# ff.net
KiCad netlist of a schematic drawn in Altium Designer
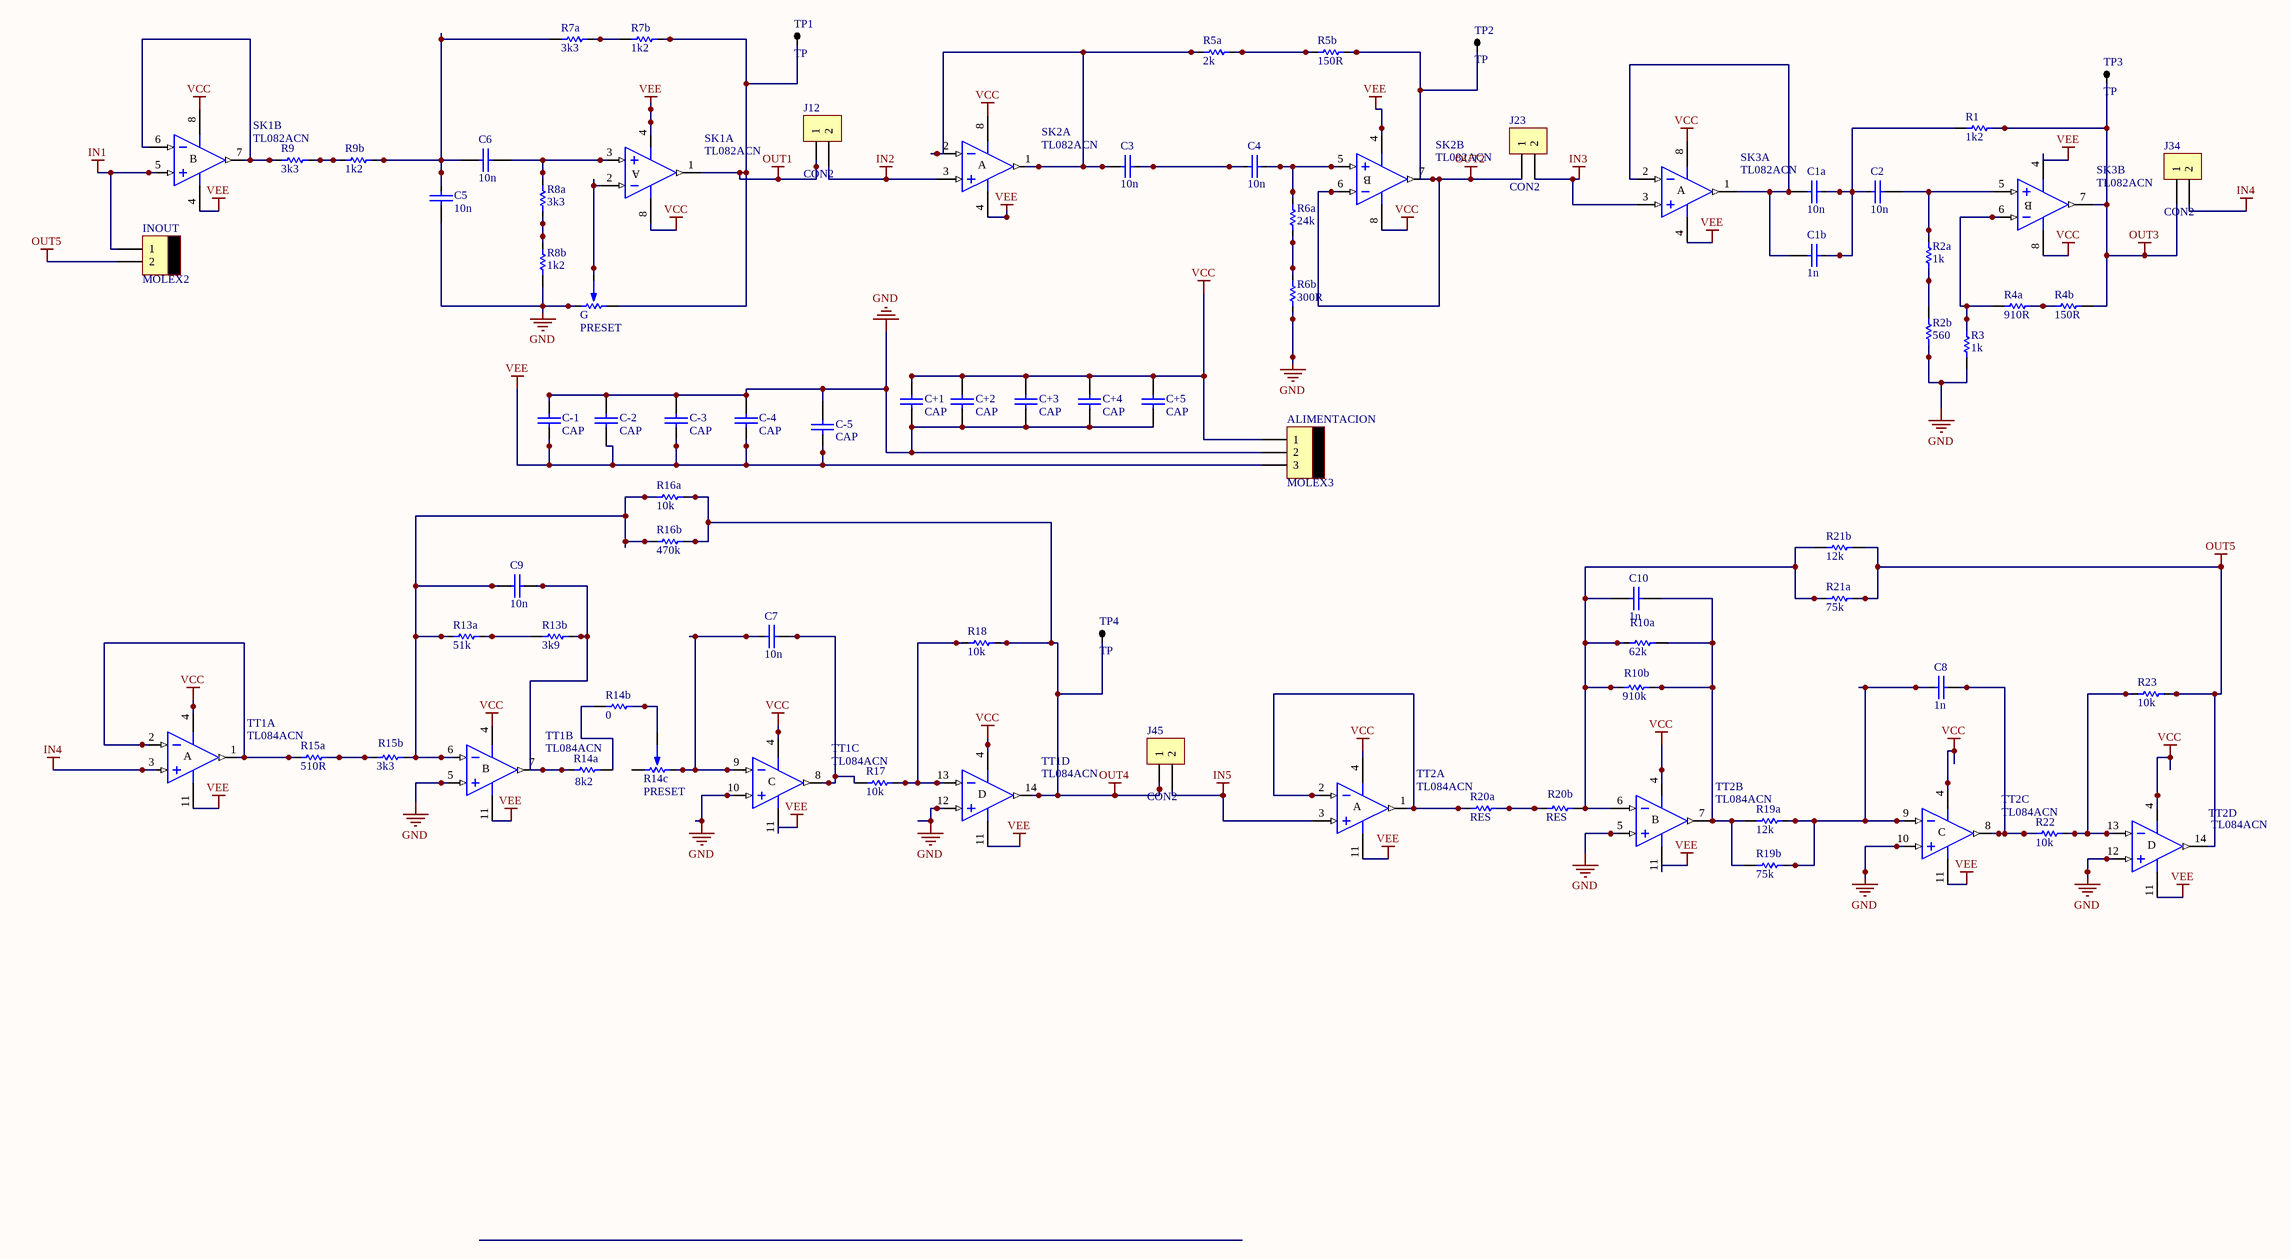
[diagram p0: ff.SchDoc]

(export (version "E")
  (design (tool "Eeschema 10.0.6"))
  (components
    (comp (ref "ALIMENTACION")
      (value "MOLEX3")
      (footprint "MOLEX3")
      (libsource (lib "LIBEBAL") (part "MOLEX3"))
    )
    (comp (ref "C+1") (value "CAP") (footprint "CAP200") (libsource (lib "LIBEBAL") (part "CAP")))
    (comp (ref "C+2") (value "CAP") (footprint "CAP200") (libsource (lib "LIBEBAL") (part "CAP")))
    (comp (ref "C+3") (value "CAP") (footprint "CAP200") (libsource (lib "LIBEBAL") (part "CAP")))
    (comp (ref "C+4") (value "CAP") (footprint "CAP200") (libsource (lib "LIBEBAL") (part "CAP")))
    (comp (ref "C+5") (value "CAP") (footprint "CAP200") (libsource (lib "LIBEBAL") (part "CAP")))
    (comp (ref "C-1") (value "CAP") (footprint "CAP200") (libsource (lib "LIBEBAL") (part "CAP")))
    (comp (ref "C-2") (value "CAP") (footprint "CAP200") (libsource (lib "LIBEBAL") (part "CAP")))
    (comp (ref "C-3") (value "CAP") (footprint "CAP200") (libsource (lib "LIBEBAL") (part "CAP")))
    (comp (ref "C-4") (value "CAP") (footprint "CAP200") (libsource (lib "LIBEBAL") (part "CAP")))
    (comp (ref "C-5") (value "CAP") (footprint "CAP200") (libsource (lib "LIBEBAL") (part "CAP")))
    (comp (ref "C1a") (value "10n") (footprint "CAP200") (libsource (lib "LIBEBAL") (part "CAP")))
    (comp (ref "C1b") (value "1n") (footprint "CAP200") (libsource (lib "LIBEBAL") (part "CAP")))
    (comp (ref "C2") (value "10n") (footprint "CAP200") (libsource (lib "LIBEBAL") (part "CAP")))
    (comp (ref "C3") (value "10n") (footprint "CAP200") (libsource (lib "LIBEBAL") (part "CAP")))
    (comp (ref "C4") (value "10n") (footprint "CAP200") (libsource (lib "LIBEBAL") (part "CAP")))
    (comp (ref "C5") (value "10n") (footprint "CAP200") (libsource (lib "LIBEBAL") (part "CAP")))
    (comp (ref "C6") (value "10n") (footprint "CAP200") (libsource (lib "LIBEBAL") (part "CAP")))
    (comp (ref "C7") (value "10n") (footprint "CAP200") (libsource (lib "LIBEBAL") (part "CAP")))
    (comp (ref "C8") (value "1n") (footprint "CAP200") (libsource (lib "LIBEBAL") (part "CAP")))
    (comp (ref "C9") (value "10n") (footprint "CAP200") (libsource (lib "LIBEBAL") (part "CAP")))
    (comp (ref "C10") (value "1n") (footprint "CAP200") (libsource (lib "LIBEBAL") (part "CAP")))
    (comp (ref "G") (value "PRESET") (footprint "PRESET V") (libsource (lib "LIBEBAL") (part "PRESET")))
    (comp (ref "INOUT") (value "MOLEX2") (footprint "MOLEX2") (libsource (lib "LIBEBAL") (part "MOLEX2")))
    (comp (ref "J12") (value "CON2") (footprint "SIP2") (libsource (lib "LIBEBAL") (part "CON2")))
    (comp (ref "J23") (value "CON2") (footprint "SIP2") (libsource (lib "LIBEBAL") (part "CON2")))
    (comp (ref "J34") (value "CON2") (footprint "SIP2") (libsource (lib "LIBEBAL") (part "CON2")))
    (comp (ref "J45") (value "CON2") (footprint "SIP2") (libsource (lib "LIBEBAL") (part "CON2")))
    (comp (ref "R1") (value "1k2") (footprint "0805") (libsource (lib "LIBEBAL") (part "RES")))
    (comp (ref "R2a") (value "1k") (footprint "0805") (libsource (lib "LIBEBAL") (part "RES")))
    (comp (ref "R2b") (value "560") (footprint "0805") (libsource (lib "LIBEBAL") (part "RES")))
    (comp (ref "R3") (value "1k") (footprint "0805") (libsource (lib "LIBEBAL") (part "RES")))
    (comp (ref "R4a") (value "910R") (footprint "0805") (libsource (lib "LIBEBAL") (part "RES")))
    (comp (ref "R4b") (value "150R") (footprint "0805") (libsource (lib "LIBEBAL") (part "RES")))
    (comp (ref "R5a") (value "2k") (footprint "0805") (libsource (lib "LIBEBAL") (part "RES")))
    (comp (ref "R5b") (value "150R") (footprint "0805") (libsource (lib "LIBEBAL") (part "RES")))
    (comp (ref "R6a") (value "24k") (footprint "0805") (libsource (lib "LIBEBAL") (part "RES")))
    (comp (ref "R6b") (value "300R") (footprint "0805") (libsource (lib "LIBEBAL") (part "RES")))
    (comp (ref "R7a") (value "3k3") (footprint "0805") (libsource (lib "LIBEBAL") (part "RES")))
    (comp (ref "R7b") (value "1k2") (footprint "0805") (libsource (lib "LIBEBAL") (part "RES")))
    (comp (ref "R8a") (value "3k3") (footprint "0805") (libsource (lib "LIBEBAL") (part "RES")))
    (comp (ref "R8b") (value "1k2") (footprint "0805") (libsource (lib "LIBEBAL") (part "RES")))
    (comp (ref "R9") (value "3k3") (footprint "0805") (libsource (lib "LIBEBAL") (part "RES")))
    (comp (ref "R9b") (value "1k2") (footprint "0805") (libsource (lib "LIBEBAL") (part "RES")))
    (comp (ref "R10a") (value "62k") (footprint "0805") (libsource (lib "LIBEBAL") (part "RES")))
    (comp (ref "R10b") (value "910k") (footprint "0805") (libsource (lib "LIBEBAL") (part "RES")))
    (comp (ref "R13a") (value "51k") (footprint "0805") (libsource (lib "LIBEBAL") (part "RES")))
    (comp (ref "R13b") (value "3k9") (footprint "0805") (libsource (lib "LIBEBAL") (part "RES")))
    (comp (ref "R14a") (value "8k2") (footprint "0805") (libsource (lib "LIBEBAL") (part "RES")))
    (comp (ref "R14b") (value "0") (footprint "0805") (libsource (lib "LIBEBAL") (part "RES")))
    (comp (ref "R14c") (value "PRESET") (footprint "PRESET V") (libsource (lib "LIBEBAL") (part "PRESET")))
    (comp (ref "R15a") (value "510R") (footprint "0805") (libsource (lib "LIBEBAL") (part "RES")))
    (comp (ref "R15b") (value "3k3") (footprint "0805") (libsource (lib "LIBEBAL") (part "RES")))
    (comp (ref "R16a") (value "10k") (footprint "0805") (libsource (lib "LIBEBAL") (part "RES")))
    (comp (ref "R16b") (value "470k") (footprint "0805") (libsource (lib "LIBEBAL") (part "RES")))
    (comp (ref "R17") (value "10k") (footprint "0805") (libsource (lib "LIBEBAL") (part "RES")))
    (comp (ref "R18") (value "10k") (footprint "0805") (libsource (lib "LIBEBAL") (part "RES")))
    (comp (ref "R19a") (value "12k") (footprint "0805") (libsource (lib "LIBEBAL") (part "RES")))
    (comp (ref "R19b") (value "75k") (footprint "0805") (libsource (lib "LIBEBAL") (part "RES")))
    (comp (ref "R20a") (value "RES") (footprint "0805") (libsource (lib "LIBEBAL") (part "RES")))
    (comp (ref "R20b") (value "RES") (footprint "0805") (libsource (lib "LIBEBAL") (part "RES")))
    (comp (ref "R21a") (value "75k") (footprint "0805") (libsource (lib "LIBEBAL") (part "RES")))
    (comp (ref "R21b") (value "12k") (footprint "0805") (libsource (lib "LIBEBAL") (part "RES")))
    (comp (ref "R22") (value "10k") (footprint "0805") (libsource (lib "LIBEBAL") (part "RES")))
    (comp (ref "R23") (value "10k") (footprint "0805") (libsource (lib "LIBEBAL") (part "RES")))
    (comp (ref "SK1")
      (value "TL082ACN")
      (footprint "DIP8")
      (description "General-Purpose J-FET Dual Operational Amplifier")
      (fields (field (name "PUBLISHER") "Altium Limited"))
      (libsource (lib "ST Operational Amplifier") (part "TL082ACN"))
    )
    (comp (ref "SK2")
      (value "TL082ACN")
      (footprint "DIP8")
      (description "General-Purpose J-FET Dual Operational Amplifier")
      (fields (field (name "PUBLISHER") "Altium Limited"))
      (libsource (lib "ST Operational Amplifier") (part "TL082ACN"))
    )
    (comp (ref "SK3")
      (value "TL082ACN")
      (footprint "DIP8")
      (description "General-Purpose J-FET Dual Operational Amplifier")
      (fields (field (name "PUBLISHER") "Altium Limited"))
      (libsource (lib "ST Operational Amplifier") (part "TL082ACN"))
    )
    (comp (ref "TP1") (value "TP") (footprint "TPTH") (libsource (lib "LIBEBAL") (part "TP")))
    (comp (ref "TP2") (value "TP") (footprint "TPTH") (libsource (lib "LIBEBAL") (part "TP")))
    (comp (ref "TP3") (value "TP") (footprint "TPTH") (libsource (lib "LIBEBAL") (part "TP")))
    (comp (ref "TP4") (value "TP") (footprint "TPTH") (libsource (lib "LIBEBAL") (part "TP")))
    (comp (ref "TT1")
      (value "TL084ACN")
      (footprint "DIP14")
      (description "General-Purpose J-FET Quad Operational Amplifier")
      (fields (field (name "PUBLISHER") "Altium Limited"))
      (libsource (lib "ST Operational Amplifier") (part "TL084ACN"))
    )
    (comp (ref "TT2")
      (value "TL084ACN")
      (footprint "DIP14")
      (description "General-Purpose J-FET Quad Operational Amplifier")
      (fields (field (name "PUBLISHER") "Altium Limited"))
      (libsource (lib "ST Operational Amplifier") (part "TL084ACN"))
    )
  )
  (nets
    (net (code "1") (name "GND") (class "Default")
      (node (ref "ALIMENTACION") (pin "2") (pinfunction "2_2") (pintype "passive"))
      (node (ref "C+1") (pin "2") (pinfunction "2_2") (pintype "passive"))
      (node (ref "C+2") (pin "2") (pinfunction "2_2") (pintype "passive"))
      (node (ref "C+3") (pin "2") (pinfunction "2_2") (pintype "passive"))
      (node (ref "C+4") (pin "2") (pinfunction "2_2") (pintype "passive"))
      (node (ref "C+5") (pin "2") (pinfunction "2_2") (pintype "passive"))
      (node (ref "C-1") (pin "1") (pinfunction "1_1") (pintype "passive"))
      (node (ref "C-2") (pin "1") (pinfunction "1_1") (pintype "passive"))
      (node (ref "C-3") (pin "1") (pinfunction "1_1") (pintype "passive"))
      (node (ref "C-4") (pin "1") (pinfunction "1_1") (pintype "passive"))
      (node (ref "C-5") (pin "1") (pinfunction "1_1") (pintype "passive"))
      (node (ref "C5") (pin "1") (pinfunction "1_1") (pintype "passive"))
      (node (ref "G") (pin "1") (pinfunction "1_1") (pintype "passive"))
      (node (ref "R2b") (pin "1") (pinfunction "1_1") (pintype "passive"))
      (node (ref "R3") (pin "1") (pinfunction "1_1") (pintype "passive"))
      (node (ref "R6b") (pin "1") (pinfunction "1_1") (pintype "passive"))
      (node (ref "R8b") (pin "1") (pinfunction "1_1") (pintype "passive"))
      (node (ref "TT1") (pin "10") (pinfunction "IN+_10") (pintype "input"))
      (node (ref "TT1") (pin "12") (pinfunction "IN+_12") (pintype "input"))
      (node (ref "TT1") (pin "5") (pinfunction "IN+_5") (pintype "input"))
      (node (ref "TT2") (pin "10") (pinfunction "IN+_10") (pintype "input"))
      (node (ref "TT2") (pin "12") (pinfunction "IN+_12") (pintype "input"))
      (node (ref "TT2") (pin "5") (pinfunction "IN+_5") (pintype "input"))
    )
    (net (code "2") (name "IN1") (class "Default")
      (node (ref "INOUT") (pin "1") (pinfunction "1_1") (pintype "passive"))
      (node (ref "SK1") (pin "5") (pinfunction "IN+_5") (pintype "input"))
    )
    (net (code "3") (name "IN2") (class "Default")
      (node (ref "J12") (pin "2") (pinfunction "2_2") (pintype "passive"))
      (node (ref "SK2") (pin "3") (pinfunction "IN+_3") (pintype "input"))
    )
    (net (code "4") (name "IN3") (class "Default")
      (node (ref "J23") (pin "2") (pinfunction "2_2") (pintype "passive"))
      (node (ref "SK3") (pin "3") (pinfunction "IN+_3") (pintype "input"))
    )
    (net (code "5") (name "IN4") (class "Default")
      (node (ref "J34") (pin "2") (pinfunction "2_2") (pintype "passive"))
      (node (ref "TT1") (pin "3") (pinfunction "IN+_3") (pintype "input"))
    )
    (net (code "6") (name "IN5") (class "Default")
      (node (ref "J45") (pin "2") (pinfunction "2_2") (pintype "passive"))
      (node (ref "TT2") (pin "3") (pinfunction "IN+_3") (pintype "input"))
    )
    (net (code "7") (name "Net-(C1a-Pad2)") (class "Default")
      (node (ref "C1a") (pin "2") (pinfunction "2_2") (pintype "passive"))
      (node (ref "C1b") (pin "2") (pinfunction "2_2") (pintype "passive"))
      (node (ref "C2") (pin "1") (pinfunction "1_1") (pintype "passive"))
      (node (ref "R1") (pin "1") (pinfunction "1_1") (pintype "passive"))
    )
    (net (code "8") (name "Net-(C3-Pad2)") (class "Default")
      (node (ref "C3") (pin "2") (pinfunction "2_2") (pintype "passive"))
      (node (ref "C4") (pin "1") (pinfunction "1_1") (pintype "passive"))
    )
    (net (code "9") (name "Net-(C5-Pad2)") (class "Default")
      (node (ref "C5") (pin "2") (pinfunction "2_2") (pintype "passive"))
      (node (ref "C6") (pin "2") (pinfunction "2_2") (pintype "passive"))
      (node (ref "R7a") (pin "1") (pinfunction "1_1") (pintype "passive"))
      (node (ref "R9b") (pin "2") (pinfunction "2_2") (pintype "passive"))
    )
    (net (code "10") (name "Net-(R2a-Pad1)") (class "Default")
      (node (ref "R2a") (pin "1") (pinfunction "1_1") (pintype "passive"))
      (node (ref "R2b") (pin "2") (pinfunction "2_2") (pintype "passive"))
    )
    (net (code "11") (name "Net-(R4a-Pad1)") (class "Default")
      (node (ref "R4a") (pin "1") (pinfunction "1_1") (pintype "passive"))
      (node (ref "R4b") (pin "2") (pinfunction "2_2") (pintype "passive"))
    )
    (net (code "12") (name "Net-(R5a-Pad2)") (class "Default")
      (node (ref "R5a") (pin "2") (pinfunction "2_2") (pintype "passive"))
      (node (ref "R5b") (pin "1") (pinfunction "1_1") (pintype "passive"))
    )
    (net (code "13") (name "Net-(R6a-Pad1)") (class "Default")
      (node (ref "R6a") (pin "1") (pinfunction "1_1") (pintype "passive"))
      (node (ref "R6b") (pin "2") (pinfunction "2_2") (pintype "passive"))
    )
    (net (code "14") (name "Net-(R7a-Pad2)") (class "Default")
      (node (ref "R7a") (pin "2") (pinfunction "2_2") (pintype "passive"))
      (node (ref "R7b") (pin "2") (pinfunction "2_2") (pintype "passive"))
    )
    (net (code "15") (name "Net-(R8a-Pad1)") (class "Default")
      (node (ref "R8a") (pin "1") (pinfunction "1_1") (pintype "passive"))
      (node (ref "R8b") (pin "2") (pinfunction "2_2") (pintype "passive"))
    )
    (net (code "16") (name "Net-(R9-Pad1)") (class "Default")
      (node (ref "R9") (pin "1") (pinfunction "1_1") (pintype "passive"))
      (node (ref "R9b") (pin "1") (pinfunction "1_1") (pintype "passive"))
    )
    (net (code "17") (name "Net-(R13a-Pad2)") (class "Default")
      (node (ref "R13a") (pin "2") (pinfunction "2_2") (pintype "passive"))
      (node (ref "R13b") (pin "1") (pinfunction "1_1") (pintype "passive"))
    )
    (net (code "18") (name "Net-(R14a-Pad2)") (class "Default")
      (node (ref "R14a") (pin "2") (pinfunction "2_2") (pintype "passive"))
      (node (ref "R14b") (pin "1") (pinfunction "1_1") (pintype "passive"))
    )
    (net (code "19") (name "Net-(R14b-Pad2)") (class "Default")
      (node (ref "R14b") (pin "2") (pinfunction "2_2") (pintype "passive"))
      (node (ref "R14c") (pin "2") (pinfunction "2_2") (pintype "passive"))
    )
    (net (code "20") (name "Net-(R15a-Pad2)") (class "Default")
      (node (ref "R15a") (pin "2") (pinfunction "2_2") (pintype "passive"))
      (node (ref "R15b") (pin "1") (pinfunction "1_1") (pintype "passive"))
    )
    (net (code "21") (name "Net-(R20a-Pad2)") (class "Default")
      (node (ref "R20a") (pin "2") (pinfunction "2_2") (pintype "passive"))
      (node (ref "R20b") (pin "1") (pinfunction "1_1") (pintype "passive"))
    )
    (net (code "22") (name "Net-(SK1A-IN+)") (class "Default")
      (node (ref "C6") (pin "1") (pinfunction "1_1") (pintype "passive"))
      (node (ref "R8a") (pin "2") (pinfunction "2_2") (pintype "passive"))
      (node (ref "SK1") (pin "3") (pinfunction "IN+_3") (pintype "input"))
    )
    (net (code "23") (name "Net-(SK1A-IN-)") (class "Default")
      (node (ref "G") (pin "2") (pinfunction "2_2") (pintype "passive"))
      (node (ref "SK1") (pin "2") (pinfunction "IN-_2") (pintype "input"))
    )
    (net (code "24") (name "Net-(SK1B-IN-)") (class "Default")
      (node (ref "R9") (pin "2") (pinfunction "2_2") (pintype "passive"))
      (node (ref "SK1") (pin "6") (pinfunction "IN-_6") (pintype "input"))
      (node (ref "SK1") (pin "7") (pinfunction "OUT_7") (pintype "output"))
    )
    (net (code "25") (name "Net-(SK2A-IN-)") (class "Default")
      (node (ref "C3") (pin "1") (pinfunction "1_1") (pintype "passive"))
      (node (ref "R5a") (pin "1") (pinfunction "1_1") (pintype "passive"))
      (node (ref "SK2") (pin "1") (pinfunction "OUT_1") (pintype "output"))
      (node (ref "SK2") (pin "2") (pinfunction "IN-_2") (pintype "input"))
    )
    (net (code "26") (name "Net-(SK2B-IN+)") (class "Default")
      (node (ref "C4") (pin "2") (pinfunction "2_2") (pintype "passive"))
      (node (ref "R6a") (pin "2") (pinfunction "2_2") (pintype "passive"))
      (node (ref "SK2") (pin "5") (pinfunction "IN+_5") (pintype "input"))
    )
    (net (code "27") (name "Net-(SK3A-IN-)") (class "Default")
      (node (ref "C1a") (pin "1") (pinfunction "1_1") (pintype "passive"))
      (node (ref "C1b") (pin "1") (pinfunction "1_1") (pintype "passive"))
      (node (ref "SK3") (pin "1") (pinfunction "OUT_1") (pintype "output"))
      (node (ref "SK3") (pin "2") (pinfunction "IN-_2") (pintype "input"))
    )
    (net (code "28") (name "Net-(SK3B-IN+)") (class "Default")
      (node (ref "C2") (pin "2") (pinfunction "2_2") (pintype "passive"))
      (node (ref "R2a") (pin "2") (pinfunction "2_2") (pintype "passive"))
      (node (ref "SK3") (pin "5") (pinfunction "IN+_5") (pintype "input"))
    )
    (net (code "29") (name "Net-(SK3B-IN-)") (class "Default")
      (node (ref "R3") (pin "2") (pinfunction "2_2") (pintype "passive"))
      (node (ref "R4a") (pin "2") (pinfunction "2_2") (pintype "passive"))
      (node (ref "SK3") (pin "6") (pinfunction "IN-_6") (pintype "input"))
    )
    (net (code "30") (name "Net-(TT1A-IN-)") (class "Default")
      (node (ref "R15a") (pin "1") (pinfunction "1_1") (pintype "passive"))
      (node (ref "TT1") (pin "1") (pinfunction "OUT_1") (pintype "output"))
      (node (ref "TT1") (pin "2") (pinfunction "IN-_2") (pintype "input"))
    )
    (net (code "31") (name "Net-(TT1B-IN-)") (class "Default")
      (node (ref "C9") (pin "1") (pinfunction "1_1") (pintype "passive"))
      (node (ref "R13a") (pin "1") (pinfunction "1_1") (pintype "passive"))
      (node (ref "R15b") (pin "2") (pinfunction "2_2") (pintype "passive"))
      (node (ref "R16a") (pin "1") (pinfunction "1_1") (pintype "passive"))
      (node (ref "R16b") (pin "1") (pinfunction "1_1") (pintype "passive"))
      (node (ref "TT1") (pin "6") (pinfunction "IN-_6") (pintype "input"))
    )
    (net (code "32") (name "Net-(TT1B-OUT)") (class "Default")
      (node (ref "C9") (pin "2") (pinfunction "2_2") (pintype "passive"))
      (node (ref "R13b") (pin "2") (pinfunction "2_2") (pintype "passive"))
      (node (ref "R14a") (pin "1") (pinfunction "1_1") (pintype "passive"))
      (node (ref "TT1") (pin "7") (pinfunction "OUT_7") (pintype "output"))
    )
    (net (code "33") (name "Net-(TT1C-IN-)") (class "Default")
      (node (ref "C7") (pin "1") (pinfunction "1_1") (pintype "passive"))
      (node (ref "R14c") (pin "3") (pinfunction "3_3") (pintype "passive"))
      (node (ref "TT1") (pin "9") (pinfunction "IN-_9") (pintype "input"))
    )
    (net (code "34") (name "Net-(TT1C-OUT)") (class "Default")
      (node (ref "C7") (pin "2") (pinfunction "2_2") (pintype "passive"))
      (node (ref "R17") (pin "1") (pinfunction "1_1") (pintype "passive"))
      (node (ref "TT1") (pin "8") (pinfunction "OUT_8") (pintype "output"))
    )
    (net (code "35") (name "Net-(TT1D-IN-)") (class "Default")
      (node (ref "R17") (pin "2") (pinfunction "2_2") (pintype "passive"))
      (node (ref "R18") (pin "1") (pinfunction "1_1") (pintype "passive"))
      (node (ref "TT1") (pin "13") (pinfunction "IN-_13") (pintype "input"))
    )
    (net (code "36") (name "Net-(TT2A-IN-)") (class "Default")
      (node (ref "R20a") (pin "1") (pinfunction "1_1") (pintype "passive"))
      (node (ref "TT2") (pin "1") (pinfunction "OUT_1") (pintype "output"))
      (node (ref "TT2") (pin "2") (pinfunction "IN-_2") (pintype "input"))
    )
    (net (code "37") (name "Net-(TT2B-IN-)") (class "Default")
      (node (ref "C10") (pin "1") (pinfunction "1_1") (pintype "passive"))
      (node (ref "R10a") (pin "1") (pinfunction "1_1") (pintype "passive"))
      (node (ref "R10b") (pin "1") (pinfunction "1_1") (pintype "passive"))
      (node (ref "R20b") (pin "2") (pinfunction "2_2") (pintype "passive"))
      (node (ref "R21a") (pin "1") (pinfunction "1_1") (pintype "passive"))
      (node (ref "R21b") (pin "1") (pinfunction "1_1") (pintype "passive"))
      (node (ref "TT2") (pin "6") (pinfunction "IN-_6") (pintype "input"))
    )
    (net (code "38") (name "Net-(TT2B-OUT)") (class "Default")
      (node (ref "C10") (pin "2") (pinfunction "2_2") (pintype "passive"))
      (node (ref "R10a") (pin "2") (pinfunction "2_2") (pintype "passive"))
      (node (ref "R10b") (pin "2") (pinfunction "2_2") (pintype "passive"))
      (node (ref "R19a") (pin "1") (pinfunction "1_1") (pintype "passive"))
      (node (ref "R19b") (pin "1") (pinfunction "1_1") (pintype "passive"))
      (node (ref "TT2") (pin "7") (pinfunction "OUT_7") (pintype "output"))
    )
    (net (code "39") (name "Net-(TT2C-IN-)") (class "Default")
      (node (ref "C8") (pin "1") (pinfunction "1_1") (pintype "passive"))
      (node (ref "R19a") (pin "2") (pinfunction "2_2") (pintype "passive"))
      (node (ref "R19b") (pin "2") (pinfunction "2_2") (pintype "passive"))
      (node (ref "TT2") (pin "9") (pinfunction "IN-_9") (pintype "input"))
    )
    (net (code "40") (name "Net-(TT2C-OUT)") (class "Default")
      (node (ref "C8") (pin "2") (pinfunction "2_2") (pintype "passive"))
      (node (ref "R22") (pin "1") (pinfunction "1_1") (pintype "passive"))
      (node (ref "TT2") (pin "8") (pinfunction "OUT_8") (pintype "output"))
    )
    (net (code "41") (name "Net-(TT2D-IN-)") (class "Default")
      (node (ref "R22") (pin "2") (pinfunction "2_2") (pintype "passive"))
      (node (ref "R23") (pin "1") (pinfunction "1_1") (pintype "passive"))
      (node (ref "TT2") (pin "13") (pinfunction "IN-_13") (pintype "input"))
    )
    (net (code "42") (name "OUT1") (class "Default")
      (node (ref "G") (pin "3") (pinfunction "3_3") (pintype "passive"))
      (node (ref "J12") (pin "1") (pinfunction "1_1") (pintype "passive"))
      (node (ref "R7b") (pin "1") (pinfunction "1_1") (pintype "passive"))
      (node (ref "SK1") (pin "1") (pinfunction "OUT_1") (pintype "output"))
      (node (ref "TP1") (pin "1") (pinfunction "1_1") (pintype "passive"))
    )
    (net (code "43") (name "OUT2") (class "Default")
      (node (ref "J23") (pin "1") (pinfunction "1_1") (pintype "passive"))
      (node (ref "R5b") (pin "2") (pinfunction "2_2") (pintype "passive"))
      (node (ref "SK2") (pin "6") (pinfunction "IN-_6") (pintype "input"))
      (node (ref "SK2") (pin "7") (pinfunction "OUT_7") (pintype "output"))
      (node (ref "TP2") (pin "1") (pinfunction "1_1") (pintype "passive"))
    )
    (net (code "44") (name "OUT3") (class "Default")
      (node (ref "J34") (pin "1") (pinfunction "1_1") (pintype "passive"))
      (node (ref "R1") (pin "2") (pinfunction "2_2") (pintype "passive"))
      (node (ref "R4b") (pin "1") (pinfunction "1_1") (pintype "passive"))
      (node (ref "SK3") (pin "7") (pinfunction "OUT_7") (pintype "output"))
      (node (ref "TP3") (pin "1") (pinfunction "1_1") (pintype "passive"))
    )
    (net (code "45") (name "OUT4") (class "Default")
      (node (ref "J45") (pin "1") (pinfunction "1_1") (pintype "passive"))
      (node (ref "R16a") (pin "2") (pinfunction "2_2") (pintype "passive"))
      (node (ref "R16b") (pin "2") (pinfunction "2_2") (pintype "passive"))
      (node (ref "R18") (pin "2") (pinfunction "2_2") (pintype "passive"))
      (node (ref "TP4") (pin "1") (pinfunction "1_1") (pintype "passive"))
      (node (ref "TT1") (pin "14") (pinfunction "OUT_14") (pintype "output"))
    )
    (net (code "46") (name "OUT5") (class "Default")
      (node (ref "INOUT") (pin "2") (pinfunction "2_2") (pintype "passive"))
      (node (ref "R21a") (pin "2") (pinfunction "2_2") (pintype "passive"))
      (node (ref "R21b") (pin "2") (pinfunction "2_2") (pintype "passive"))
      (node (ref "R23") (pin "2") (pinfunction "2_2") (pintype "passive"))
      (node (ref "TT2") (pin "14") (pinfunction "OUT_14") (pintype "output"))
    )
    (net (code "47") (name "VCC") (class "Default")
      (node (ref "ALIMENTACION") (pin "1") (pinfunction "1_1") (pintype "passive"))
      (node (ref "C+1") (pin "1") (pinfunction "1_1") (pintype "passive"))
      (node (ref "C+2") (pin "1") (pinfunction "1_1") (pintype "passive"))
      (node (ref "C+3") (pin "1") (pinfunction "1_1") (pintype "passive"))
      (node (ref "C+4") (pin "1") (pinfunction "1_1") (pintype "passive"))
      (node (ref "C+5") (pin "1") (pinfunction "1_1") (pintype "passive"))
      (node (ref "SK1") (pin "8") (pinfunction "V+_8") (pintype "power_in"))
      (node (ref "SK2") (pin "8") (pinfunction "V+_8") (pintype "power_in"))
      (node (ref "SK3") (pin "8") (pinfunction "V+_8") (pintype "power_in"))
      (node (ref "TT1") (pin "4") (pinfunction "V+_4") (pintype "power_in"))
      (node (ref "TT2") (pin "4") (pinfunction "V+_4") (pintype "power_in"))
    )
    (net (code "48") (name "VEE") (class "Default")
      (node (ref "ALIMENTACION") (pin "3") (pinfunction "3_3") (pintype "passive"))
      (node (ref "C-1") (pin "2") (pinfunction "2_2") (pintype "passive"))
      (node (ref "C-2") (pin "2") (pinfunction "2_2") (pintype "passive"))
      (node (ref "C-3") (pin "2") (pinfunction "2_2") (pintype "passive"))
      (node (ref "C-4") (pin "2") (pinfunction "2_2") (pintype "passive"))
      (node (ref "C-5") (pin "2") (pinfunction "2_2") (pintype "passive"))
      (node (ref "SK1") (pin "4") (pinfunction "V-_4") (pintype "power_in"))
      (node (ref "SK2") (pin "4") (pinfunction "V-_4") (pintype "power_in"))
      (node (ref "SK3") (pin "4") (pinfunction "V-_4") (pintype "power_in"))
      (node (ref "TT1") (pin "11") (pinfunction "V-_11") (pintype "power_in"))
      (node (ref "TT2") (pin "11") (pinfunction "V-_11") (pintype "power_in"))
    )
    (net (code "49") (name "unconnected-(R14c-Pad1)") (class "Default")
      (node (ref "R14c") (pin "1") (pinfunction "1_1") (pintype "passive"))
    )
    (net (code "50") (name "unconnected-(TT1B-V+-Pad4)") (class "Default")
      (node (ref "TT1") (pin "4") (pinfunction "V+_4") (pintype "power_in"))
    )
  )
)
